# 23D_ESC_DRIVER.net
KiCad netlist of a schematic drawn in Altium Designer
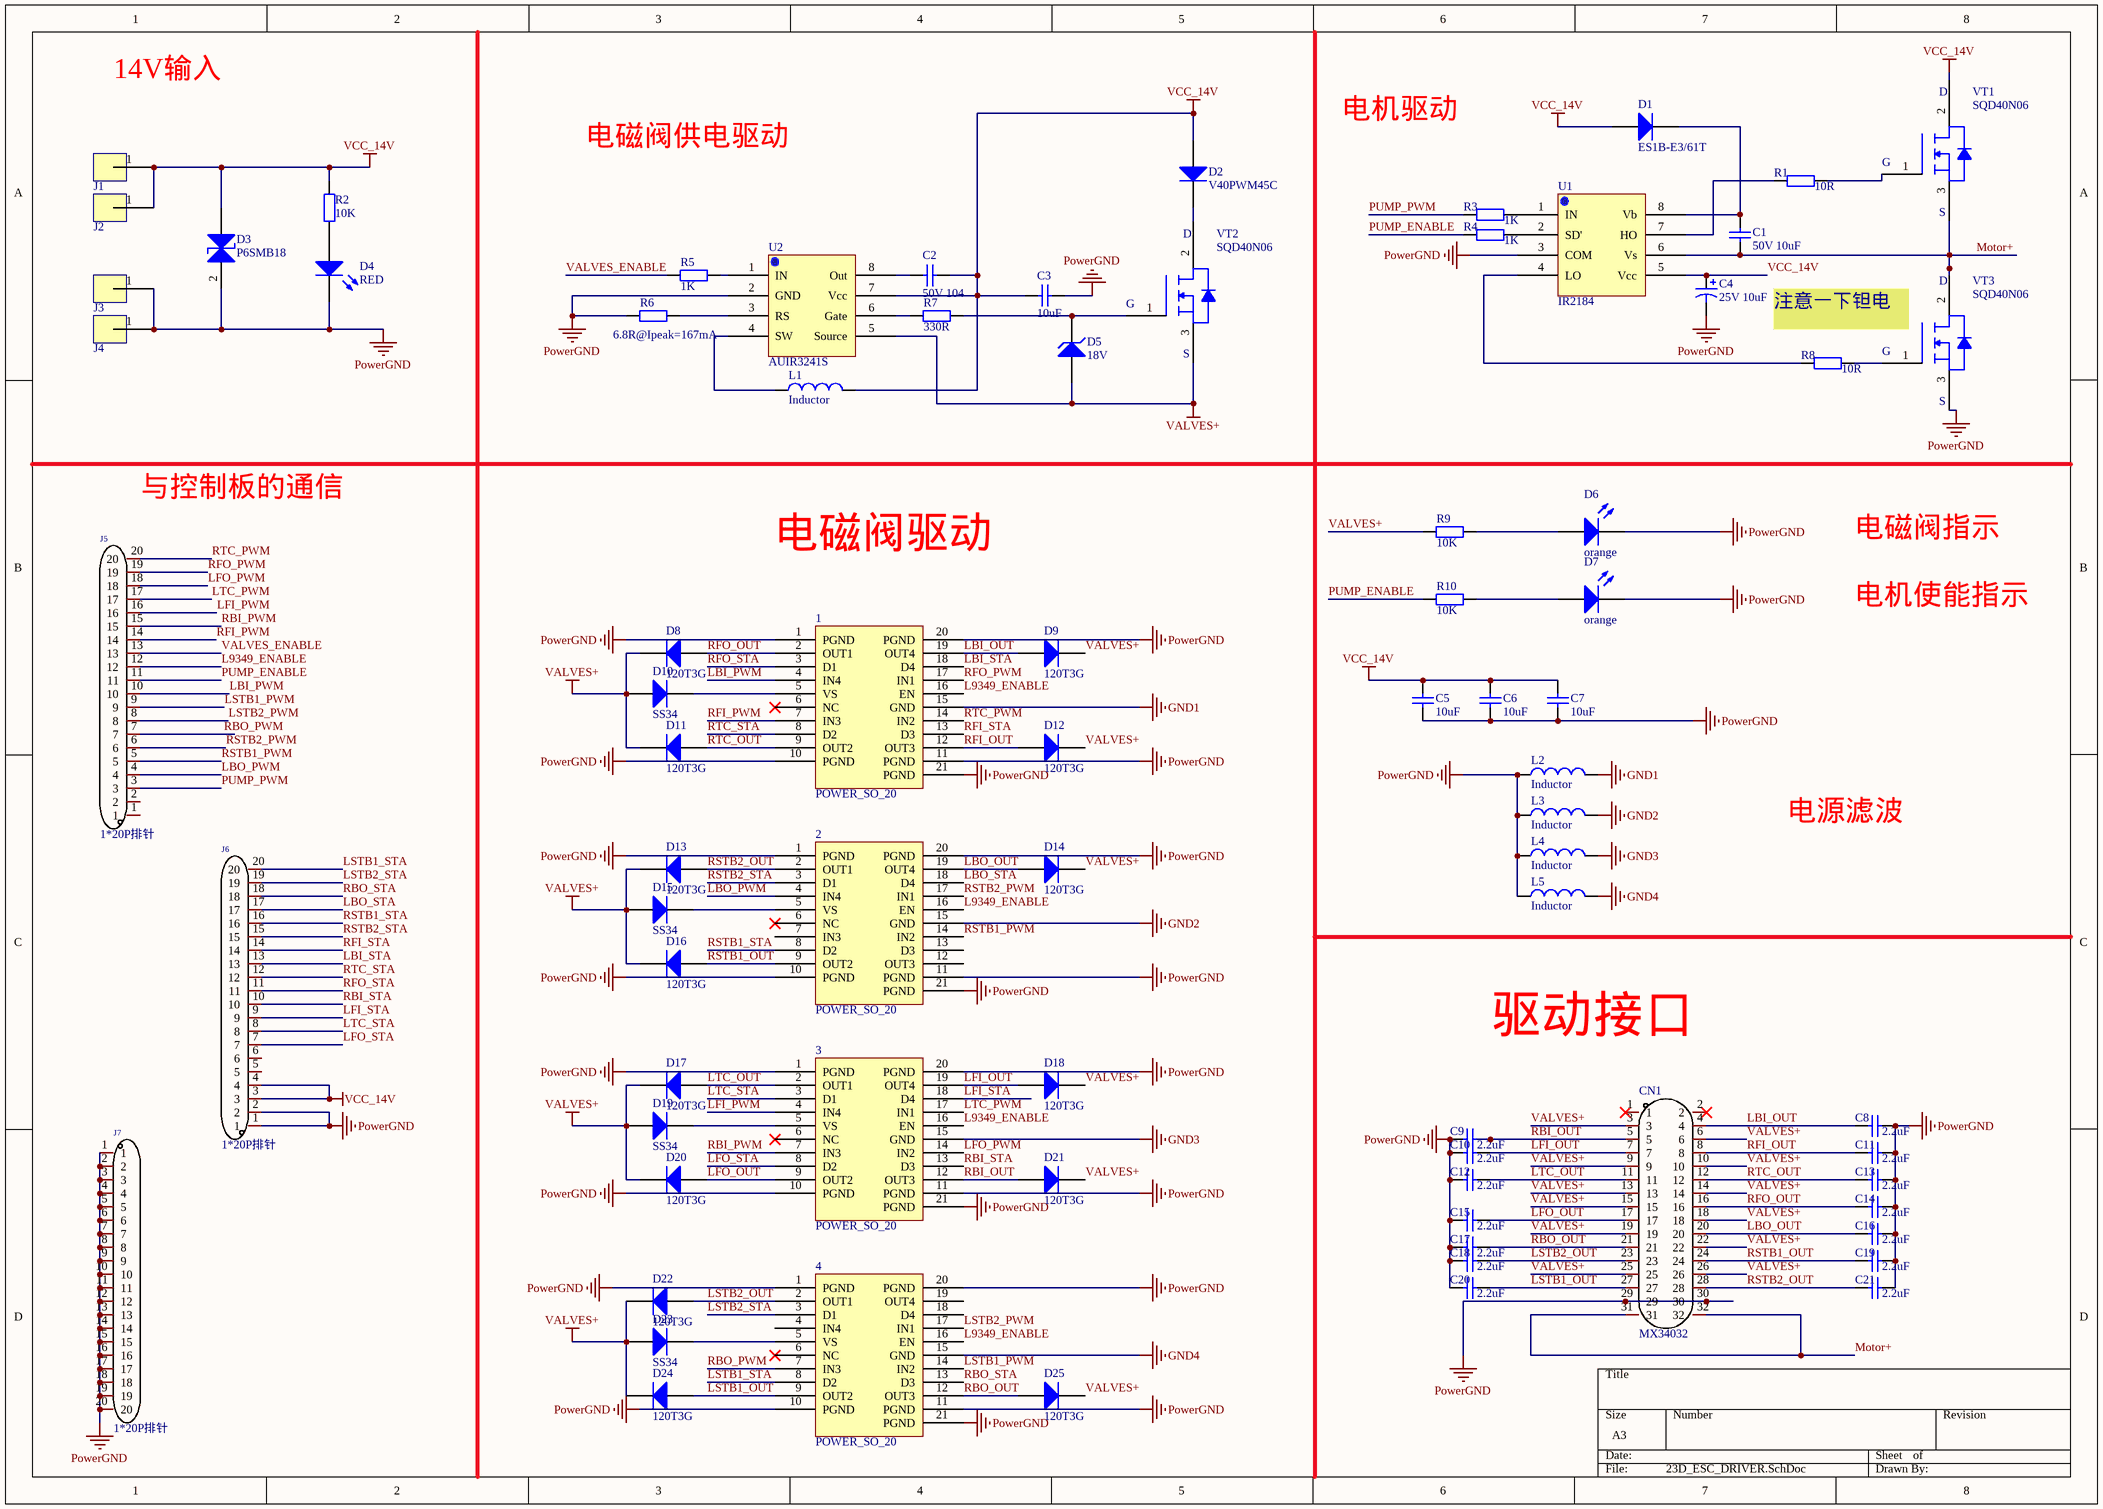
[diagram p0: 23D_ESC_DRIVER.SchDoc]

(export (version "E")
  (design (tool "Eeschema 10.0.6"))
  (components
    (comp (ref "1")
      (value "POWER_SO_20")
      (footprint "POWERSO-20_self_with3D_USEable:POWERSO-20_L15.9-W11.0-P1.27-LS14.2-BL-EP")
      (libsource (lib "PowerSO-20") (part "POWER_SO_20"))
    )
    (comp (ref "2")
      (value "POWER_SO_20")
      (footprint "POWERSO-20_self_with3D_USEable:POWERSO-20_L15.9-W11.0-P1.27-LS14.2-BL-EP")
      (libsource (lib "PowerSO-20") (part "POWER_SO_20"))
    )
    (comp (ref "3")
      (value "POWER_SO_20")
      (footprint "POWERSO-20_self_with3D_USEable:POWERSO-20_L15.9-W11.0-P1.27-LS14.2-BL-EP")
      (libsource (lib "PowerSO-20") (part "POWER_SO_20"))
    )
    (comp (ref "4")
      (value "POWER_SO_20")
      (footprint "POWERSO-20_self_with3D_USEable:POWERSO-20_L15.9-W11.0-P1.27-LS14.2-BL-EP")
      (libsource (lib "PowerSO-20") (part "POWER_SO_20"))
    )
    (comp (ref "C1")
      (value "50V 10uF")
      (footprint "C 0805")
      (description "无极性电容")
      (libsource (lib "HRT_D Schlib") (part "Cap"))
    )
    (comp (ref "C2")
      (value "50V 104")
      (footprint "C 0805")
      (description "无极性电容")
      (libsource (lib "HRT_D Schlib") (part "Cap"))
    )
    (comp (ref "C3")
      (value "10uF")
      (footprint "C 0805")
      (description "无极性电容")
      (libsource (lib "HRT_D Schlib") (part "Cap"))
    )
    (comp (ref "C4")
      (value "25V 10uF")
      (footprint "CP 3528B")
      (description "极性电容")
      (libsource (lib "ER100_ESC") (part "Cap_Pol"))
    )
    (comp (ref "C5")
      (value "10uF")
      (footprint "C 0805")
      (description "无极性电容")
      (libsource (lib "HRT_D Schlib") (part "Cap"))
    )
    (comp (ref "C6")
      (value "10uF")
      (footprint "C 0805")
      (description "无极性电容")
      (libsource (lib "HRT_D Schlib") (part "Cap"))
    )
    (comp (ref "C7")
      (value "10uF")
      (footprint "C 0805")
      (description "无极性电容")
      (libsource (lib "HRT_D Schlib") (part "Cap"))
    )
    (comp (ref "C8")
      (value "2.2uF")
      (footprint "C 0805")
      (description "无极性电容")
      (libsource (lib "HRT_D Schlib") (part "Cap"))
    )
    (comp (ref "C9")
      (value "2.2uF")
      (footprint "C 0805")
      (description "无极性电容")
      (libsource (lib "HRT_D Schlib") (part "Cap"))
    )
    (comp (ref "C10")
      (value "2.2uF")
      (footprint "C 0805")
      (description "无极性电容")
      (libsource (lib "HRT_D Schlib") (part "Cap"))
    )
    (comp (ref "C11")
      (value "2.2uF")
      (footprint "C 0805")
      (description "无极性电容")
      (libsource (lib "HRT_D Schlib") (part "Cap"))
    )
    (comp (ref "C12")
      (value "2.2uF")
      (footprint "C 0805")
      (description "无极性电容")
      (libsource (lib "HRT_D Schlib") (part "Cap"))
    )
    (comp (ref "C13")
      (value "2.2uF")
      (footprint "C 0805")
      (description "无极性电容")
      (libsource (lib "HRT_D Schlib") (part "Cap"))
    )
    (comp (ref "C14")
      (value "2.2uF")
      (footprint "C 0805")
      (description "无极性电容")
      (libsource (lib "HRT_D Schlib") (part "Cap"))
    )
    (comp (ref "C15")
      (value "2.2uF")
      (footprint "C 0805")
      (description "无极性电容")
      (libsource (lib "HRT_D Schlib") (part "Cap"))
    )
    (comp (ref "C16")
      (value "2.2uF")
      (footprint "C 0805")
      (description "无极性电容")
      (libsource (lib "HRT_D Schlib") (part "Cap"))
    )
    (comp (ref "C17")
      (value "2.2uF")
      (footprint "C 0805")
      (description "无极性电容")
      (libsource (lib "HRT_D Schlib") (part "Cap"))
    )
    (comp (ref "C18")
      (value "2.2uF")
      (footprint "C 0805")
      (description "无极性电容")
      (libsource (lib "HRT_D Schlib") (part "Cap"))
    )
    (comp (ref "C19")
      (value "2.2uF")
      (footprint "C 0805")
      (description "无极性电容")
      (libsource (lib "HRT_D Schlib") (part "Cap"))
    )
    (comp (ref "C20")
      (value "2.2uF")
      (footprint "C 0805")
      (description "无极性电容")
      (libsource (lib "HRT_D Schlib") (part "Cap"))
    )
    (comp (ref "C21")
      (value "2.2uF")
      (footprint "C 0805")
      (description "无极性电容")
      (libsource (lib "HRT_D Schlib") (part "Cap"))
    )
    (comp (ref "CN1")
      (value "MX34032NF2")
      (footprint "CONN-TH_MX34032NF2")
      (description "间距:2.2mm;插针结构:2x16P;排数:2;每排PIN数:16;行距:3mm;公母:公型插针;安装方式:弯插;")
      (fields (field (name "MANUFACTURER") "JAE(日本航空电子)") (field (name "NAME") "MX34032"))
      (libsource (lib "MX34032") (part "MX34032NF2"))
    )
    (comp (ref "D1")
      (value "ES1B-E3/61T")
      (footprint "DO-214")
      (description "二极管")
      (libsource (lib "ER100_ESC") (part "Diode"))
    )
    (comp (ref "D2")
      (value "V40PWM45C")
      (footprint "TO252_DIO")
      (description "二极管")
      (libsource (lib "ER100_ESC") (part "Diode"))
    )
    (comp (ref "D3")
      (value "P6SMB18")
      (footprint "DO-214AA")
      (description "BiDir TVS Diode")
      (libsource (lib "ER100_ESC") (part "P6SMBXX"))
    )
    (comp (ref "D4")
      (value "RED")
      (footprint "LED_0805")
      (description "发光二极管")
      (libsource (lib "ESC_control") (part "LED"))
    )
    (comp (ref "D5") (value "18V") (footprint "LL34") (libsource (lib "ER100_ESC") (part "Diode_Zener")))
    (comp (ref "D6")
      (value "orange")
      (footprint "LED_0805")
      (description "发光二极管")
      (libsource (lib "ESC_control") (part "LED"))
    )
    (comp (ref "D7")
      (value "orange")
      (footprint "LED_0805")
      (description "发光二极管")
      (libsource (lib "ESC_control") (part "LED"))
    )
    (comp (ref "D8")
      (value "120T3G")
      (footprint "DO-214")
      (description "二极管")
      (libsource (lib "ER100_ESC") (part "Diode"))
    )
    (comp (ref "D9")
      (value "120T3G")
      (footprint "DO-214")
      (description "二极管")
      (libsource (lib "ER100_ESC") (part "Diode"))
    )
    (comp (ref "D10")
      (value "SS34")
      (footprint "DO-214")
      (description "二极管")
      (libsource (lib "ESC_control") (part "Diode"))
    )
    (comp (ref "D11")
      (value "120T3G")
      (footprint "DO-214")
      (description "二极管")
      (libsource (lib "ER100_ESC") (part "Diode"))
    )
    (comp (ref "D12")
      (value "120T3G")
      (footprint "DO-214")
      (description "二极管")
      (libsource (lib "ER100_ESC") (part "Diode"))
    )
    (comp (ref "D13")
      (value "120T3G")
      (footprint "DO-214")
      (description "二极管")
      (libsource (lib "ER100_ESC") (part "Diode"))
    )
    (comp (ref "D14")
      (value "120T3G")
      (footprint "DO-214")
      (description "二极管")
      (libsource (lib "ER100_ESC") (part "Diode"))
    )
    (comp (ref "D15")
      (value "SS34")
      (footprint "DO-214")
      (description "二极管")
      (libsource (lib "ESC_control") (part "Diode"))
    )
    (comp (ref "D16")
      (value "120T3G")
      (footprint "DO-214")
      (description "二极管")
      (libsource (lib "ER100_ESC") (part "Diode"))
    )
    (comp (ref "D17")
      (value "120T3G")
      (footprint "DO-214")
      (description "二极管")
      (libsource (lib "ER100_ESC") (part "Diode"))
    )
    (comp (ref "D18")
      (value "120T3G")
      (footprint "DO-214")
      (description "二极管")
      (libsource (lib "ER100_ESC") (part "Diode"))
    )
    (comp (ref "D19")
      (value "SS34")
      (footprint "DO-214")
      (description "二极管")
      (libsource (lib "ESC_control") (part "Diode"))
    )
    (comp (ref "D20")
      (value "120T3G")
      (footprint "DO-214")
      (description "二极管")
      (libsource (lib "ER100_ESC") (part "Diode"))
    )
    (comp (ref "D21")
      (value "120T3G")
      (footprint "DO-214")
      (description "二极管")
      (libsource (lib "ER100_ESC") (part "Diode"))
    )
    (comp (ref "D22")
      (value "120T3G")
      (footprint "DO-214")
      (description "二极管")
      (libsource (lib "ER100_ESC") (part "Diode"))
    )
    (comp (ref "D23")
      (value "SS34")
      (footprint "DO-214")
      (description "二极管")
      (libsource (lib "ESC_control") (part "Diode"))
    )
    (comp (ref "D24")
      (value "120T3G")
      (footprint "DO-214")
      (description "二极管")
      (libsource (lib "ER100_ESC") (part "Diode"))
    )
    (comp (ref "D25")
      (value "120T3G")
      (footprint "DO-214")
      (description "二极管")
      (libsource (lib "ER100_ESC") (part "Diode"))
    )
    (comp (ref "J1")
      (value "SMT_Connector")
      (footprint "SMT_Connector")
      (description "表贴接线端")
      (libsource (lib "ER100_ESC") (part "SMT_Connector"))
    )
    (comp (ref "J2")
      (value "SMT_Connector")
      (footprint "SMT_Connector")
      (description "表贴接线端")
      (libsource (lib "ER100_ESC") (part "SMT_Connector"))
    )
    (comp (ref "J3")
      (value "SMT_Connector")
      (footprint "SMT_Connector")
      (description "表贴接线端")
      (libsource (lib "ER100_ESC") (part "SMT_Connector"))
    )
    (comp (ref "J4")
      (value "SMT_Connector")
      (footprint "SMT_Connector")
      (description "表贴接线端")
      (libsource (lib "ER100_ESC") (part "SMT_Connector"))
    )
    (comp (ref "J5")
      (value "2.54-1*20P直针")
      (footprint "HDR-TH_20P-P2.54-V-M-1")
      (fields (field (name "MANUFACTURER") "BOOMELE(博穆精密)") (field (name "NAME") "1*20P排针"))
      (libsource (lib "20P排针2.54mm") (part "2.54-1*20P直针"))
    )
    (comp (ref "J6")
      (value "2.54-1*20P直针")
      (footprint "HDR-TH_20P-P2.54-V-M-1")
      (fields (field (name "MANUFACTURER") "BOOMELE(博穆精密)") (field (name "NAME") "1*20P排针"))
      (libsource (lib "20P排针2.54mm") (part "2.54-1*20P直针"))
    )
    (comp (ref "J7")
      (value "2.54-1*20P直针")
      (footprint "HDR2.54-LI-20P")
      (fields (field (name "MANUFACTURER") "BOOMELE(博穆精密)") (field (name "NAME") "1*20P排针"))
      (libsource (lib "20P排针2.54mm") (part "2.54-1*20P直针"))
    )
    (comp (ref "L1")
      (value "Inductor")
      (footprint "L 0805")
      (description "电感")
      (libsource (lib "HRT_D Schlib") (part "Inductor"))
    )
    (comp (ref "L2")
      (value "Inductor")
      (footprint "L 0805")
      (description "电感")
      (libsource (lib "HRT_D Schlib") (part "Inductor"))
    )
    (comp (ref "L3")
      (value "Inductor")
      (footprint "L 0805")
      (description "电感")
      (libsource (lib "HRT_D Schlib") (part "Inductor"))
    )
    (comp (ref "L4")
      (value "Inductor")
      (footprint "L 0805")
      (description "电感")
      (libsource (lib "HRT_D Schlib") (part "Inductor"))
    )
    (comp (ref "L5")
      (value "Inductor")
      (footprint "L 0805")
      (description "电感")
      (libsource (lib "HRT_D Schlib") (part "Inductor"))
    )
    (comp (ref "R1")
      (value "10R")
      (footprint "R 0805")
      (description "电阻")
      (libsource (lib "HRT_D Schlib") (part "Resistor"))
    )
    (comp (ref "R2")
      (value "10K")
      (footprint "R 0805")
      (description "电阻")
      (libsource (lib "") (part "Resistor_1"))
    )
    (comp (ref "R3")
      (value "1K")
      (footprint "R 0805")
      (description "电阻")
      (libsource (lib "HRT_D Schlib") (part "Resistor"))
    )
    (comp (ref "R4")
      (value "1K")
      (footprint "R 0805")
      (description "电阻")
      (libsource (lib "HRT_D Schlib") (part "Resistor"))
    )
    (comp (ref "R5")
      (value "1K")
      (footprint "R 0805")
      (description "电阻")
      (libsource (lib "HRT_D Schlib") (part "Resistor"))
    )
    (comp (ref "R6")
      (value "6.8R@Ipeak=167mA")
      (footprint "R 0805")
      (description "电阻")
      (libsource (lib "HRT_D Schlib") (part "Resistor"))
    )
    (comp (ref "R7")
      (value "330R")
      (footprint "R 0805")
      (description "电阻")
      (libsource (lib "HRT_D Schlib") (part "Resistor"))
    )
    (comp (ref "R8")
      (value "10R")
      (footprint "R 0805")
      (description "电阻")
      (libsource (lib "HRT_D Schlib") (part "Resistor"))
    )
    (comp (ref "R9")
      (value "10K")
      (footprint "R 0805")
      (description "电阻")
      (libsource (lib "HRT_D Schlib") (part "Resistor"))
    )
    (comp (ref "R10")
      (value "10K")
      (footprint "R 0805")
      (description "电阻")
      (libsource (lib "HRT_D Schlib") (part "Resistor"))
    )
    (comp (ref "U1")
      (value "IR2184")
      (footprint "SOP8")
      (description "Half-Bridge Gate Driver")
      (libsource (lib "ER100_ESC") (part "IR2184"))
    )
    (comp (ref "U2")
      (value "AUIR3241S")
      (footprint "SOP8")
      (description "B2B MOSFET Driver")
      (libsource (lib "ER100_ESC") (part "AUIR3241S"))
    )
    (comp (ref "VT1")
      (value "SQD40N06")
      (footprint "TO263-3B")
      (libsource (lib "ER100_ESC") (part "PowerMos_N"))
    )
    (comp (ref "VT2")
      (value "SQD40N06")
      (footprint "TO252")
      (libsource (lib "ER100_ESC") (part "PowerMos_N"))
    )
    (comp (ref "VT3")
      (value "SQD40N06")
      (footprint "TO263-3B")
      (libsource (lib "ER100_ESC") (part "PowerMos_N"))
    )
  )
  (nets
    (net (code "1") (name "/L9349_ENABLE") (class "Default")
      (node (ref "1") (pin "16") (pinfunction "EN_16") (pintype "passive"))
      (node (ref "2") (pin "16") (pinfunction "EN_16") (pintype "passive"))
      (node (ref "3") (pin "16") (pinfunction "EN_16") (pintype "passive"))
      (node (ref "4") (pin "16") (pinfunction "EN_16") (pintype "passive"))
      (node (ref "J5") (pin "12") (pinfunction "12_12") (pintype "passive"))
    )
    (net (code "2") (name "/LBI_OUT") (class "Default")
      (node (ref "1") (pin "19") (pinfunction "OUT4_19") (pintype "passive"))
      (node (ref "C8") (pin "1") (pinfunction "1_1") (pintype "passive"))
      (node (ref "CN1") (pin "4") (pinfunction "4_4") (pintype "passive"))
      (node (ref "D9") (pin "1") (pinfunction "A_1") (pintype "passive"))
    )
    (net (code "3") (name "/LBI_PWM") (class "Default")
      (node (ref "1") (pin "4") (pinfunction "IN4_4") (pintype "passive"))
      (node (ref "J5") (pin "10") (pinfunction "10_10") (pintype "passive"))
    )
    (net (code "4") (name "/LBI_STA") (class "Default")
      (node (ref "1") (pin "18") (pinfunction "D4_18") (pintype "passive"))
      (node (ref "J6") (pin "13") (pinfunction "13_13") (pintype "passive"))
    )
    (net (code "5") (name "/LBO_OUT") (class "Default")
      (node (ref "2") (pin "19") (pinfunction "OUT4_19") (pintype "passive"))
      (node (ref "C16") (pin "1") (pinfunction "1_1") (pintype "passive"))
      (node (ref "CN1") (pin "20") (pinfunction "20_20") (pintype "passive"))
      (node (ref "D14") (pin "1") (pinfunction "A_1") (pintype "passive"))
    )
    (net (code "6") (name "/LBO_PWM") (class "Default")
      (node (ref "2") (pin "4") (pinfunction "IN4_4") (pintype "passive"))
      (node (ref "J5") (pin "4") (pinfunction "4_4") (pintype "passive"))
    )
    (net (code "7") (name "/LBO_STA") (class "Default")
      (node (ref "2") (pin "18") (pinfunction "D4_18") (pintype "passive"))
      (node (ref "J6") (pin "17") (pinfunction "17_17") (pintype "passive"))
    )
    (net (code "8") (name "/LFI_OUT") (class "Default")
      (node (ref "3") (pin "19") (pinfunction "OUT4_19") (pintype "passive"))
      (node (ref "C10") (pin "2") (pinfunction "2_2") (pintype "passive"))
      (node (ref "CN1") (pin "7") (pinfunction "7_7") (pintype "passive"))
      (node (ref "D18") (pin "1") (pinfunction "A_1") (pintype "passive"))
    )
    (net (code "9") (name "/LFI_PWM") (class "Default")
      (node (ref "3") (pin "4") (pinfunction "IN4_4") (pintype "passive"))
      (node (ref "J5") (pin "16") (pinfunction "16_16") (pintype "passive"))
    )
    (net (code "10") (name "/LFI_STA") (class "Default")
      (node (ref "3") (pin "18") (pinfunction "D4_18") (pintype "passive"))
      (node (ref "J6") (pin "9") (pinfunction "9_9") (pintype "passive"))
    )
    (net (code "11") (name "/LFO_OUT") (class "Default")
      (node (ref "3") (pin "9") (pinfunction "OUT2_9") (pintype "passive"))
      (node (ref "C15") (pin "2") (pinfunction "2_2") (pintype "passive"))
      (node (ref "CN1") (pin "17") (pinfunction "17_17") (pintype "passive"))
      (node (ref "D20") (pin "1") (pinfunction "A_1") (pintype "passive"))
    )
    (net (code "12") (name "/LFO_PWM") (class "Default")
      (node (ref "3") (pin "14") (pinfunction "IN2_14") (pintype "passive"))
      (node (ref "J5") (pin "18") (pinfunction "18_18") (pintype "passive"))
    )
    (net (code "13") (name "/LFO_STA") (class "Default")
      (node (ref "3") (pin "8") (pinfunction "D2_8") (pintype "passive"))
      (node (ref "J6") (pin "7") (pinfunction "7_7") (pintype "passive"))
    )
    (net (code "14") (name "/LSTB1_OUT") (class "Default")
      (node (ref "4") (pin "9") (pinfunction "OUT2_9") (pintype "passive"))
      (node (ref "C20") (pin "2") (pinfunction "2_2") (pintype "passive"))
      (node (ref "CN1") (pin "27") (pinfunction "27_27") (pintype "passive"))
      (node (ref "D24") (pin "1") (pinfunction "A_1") (pintype "passive"))
    )
    (net (code "15") (name "/LSTB1_PWM") (class "Default")
      (node (ref "4") (pin "14") (pinfunction "IN2_14") (pintype "passive"))
      (node (ref "J5") (pin "9") (pinfunction "9_9") (pintype "passive"))
    )
    (net (code "16") (name "/LSTB1_STA") (class "Default")
      (node (ref "4") (pin "8") (pinfunction "D2_8") (pintype "passive"))
      (node (ref "J6") (pin "20") (pinfunction "20_20") (pintype "passive"))
    )
    (net (code "17") (name "/LSTB2_OUT") (class "Default")
      (node (ref "4") (pin "2") (pinfunction "OUT1_2") (pintype "passive"))
      (node (ref "C18") (pin "2") (pinfunction "2_2") (pintype "passive"))
      (node (ref "CN1") (pin "23") (pinfunction "23_23") (pintype "passive"))
      (node (ref "D22") (pin "1") (pinfunction "A_1") (pintype "passive"))
    )
    (net (code "18") (name "/LSTB2_PWM") (class "Default")
      (node (ref "4") (pin "17") (pinfunction "IN1_17") (pintype "passive"))
      (node (ref "J5") (pin "8") (pinfunction "8_8") (pintype "passive"))
    )
    (net (code "19") (name "/LSTB2_STA") (class "Default")
      (node (ref "4") (pin "3") (pinfunction "D1_3") (pintype "passive"))
      (node (ref "J6") (pin "19") (pinfunction "19_19") (pintype "passive"))
    )
    (net (code "20") (name "/LTC_OUT") (class "Default")
      (node (ref "3") (pin "2") (pinfunction "OUT1_2") (pintype "passive"))
      (node (ref "C12") (pin "2") (pinfunction "2_2") (pintype "passive"))
      (node (ref "CN1") (pin "11") (pinfunction "11_11") (pintype "passive"))
      (node (ref "D17") (pin "1") (pinfunction "A_1") (pintype "passive"))
    )
    (net (code "21") (name "/LTC_PWM") (class "Default")
      (node (ref "3") (pin "17") (pinfunction "IN1_17") (pintype "passive"))
      (node (ref "J5") (pin "17") (pinfunction "17_17") (pintype "passive"))
    )
    (net (code "22") (name "/LTC_STA") (class "Default")
      (node (ref "3") (pin "3") (pinfunction "D1_3") (pintype "passive"))
      (node (ref "J6") (pin "8") (pinfunction "8_8") (pintype "passive"))
    )
    (net (code "23") (name "/Motor+") (class "Default")
      (node (ref "C1") (pin "1") (pinfunction "1_1") (pintype "passive"))
      (node (ref "CN1") (pin "31") (pinfunction "31_31") (pintype "passive"))
      (node (ref "CN1") (pin "32") (pinfunction "32_32") (pintype "passive"))
      (node (ref "U1") (pin "6") (pinfunction "Vs_6") (pintype "passive"))
      (node (ref "VT1") (pin "3") (pinfunction "3_3") (pintype "passive"))
      (node (ref "VT3") (pin "2") (pinfunction "2_2") (pintype "passive"))
    )
    (net (code "24") (name "/PUMP_ENABLE") (class "Default")
      (node (ref "J5") (pin "11") (pinfunction "11_11") (pintype "passive"))
      (node (ref "R10") (pin "1") (pinfunction "1_1") (pintype "passive"))
      (node (ref "R4") (pin "1") (pinfunction "1_1") (pintype "passive"))
    )
    (net (code "25") (name "/PUMP_PWM") (class "Default")
      (node (ref "J5") (pin "3") (pinfunction "3_3") (pintype "passive"))
      (node (ref "R3") (pin "1") (pinfunction "1_1") (pintype "passive"))
    )
    (net (code "26") (name "/RBI_OUT") (class "Default")
      (node (ref "3") (pin "12") (pinfunction "OUT3_12") (pintype "passive"))
      (node (ref "C9") (pin "2") (pinfunction "2_2") (pintype "passive"))
      (node (ref "CN1") (pin "5") (pinfunction "5_5") (pintype "passive"))
      (node (ref "D21") (pin "1") (pinfunction "A_1") (pintype "passive"))
    )
    (net (code "27") (name "/RBI_PWM") (class "Default")
      (node (ref "3") (pin "7") (pinfunction "IN3_7") (pintype "passive"))
      (node (ref "J5") (pin "15") (pinfunction "15_15") (pintype "passive"))
    )
    (net (code "28") (name "/RBI_STA") (class "Default")
      (node (ref "3") (pin "13") (pinfunction "D3_13") (pintype "passive"))
      (node (ref "J6") (pin "10") (pinfunction "10_10") (pintype "passive"))
    )
    (net (code "29") (name "/RBO_OUT") (class "Default")
      (node (ref "4") (pin "12") (pinfunction "OUT3_12") (pintype "passive"))
      (node (ref "C17") (pin "2") (pinfunction "2_2") (pintype "passive"))
      (node (ref "CN1") (pin "21") (pinfunction "21_21") (pintype "passive"))
      (node (ref "D25") (pin "1") (pinfunction "A_1") (pintype "passive"))
    )
    (net (code "30") (name "/RBO_PWM") (class "Default")
      (node (ref "4") (pin "7") (pinfunction "IN3_7") (pintype "passive"))
      (node (ref "J5") (pin "7") (pinfunction "7_7") (pintype "passive"))
    )
    (net (code "31") (name "/RBO_STA") (class "Default")
      (node (ref "4") (pin "13") (pinfunction "D3_13") (pintype "passive"))
      (node (ref "J6") (pin "18") (pinfunction "18_18") (pintype "passive"))
    )
    (net (code "32") (name "/RFI_OUT") (class "Default")
      (node (ref "1") (pin "12") (pinfunction "OUT3_12") (pintype "passive"))
      (node (ref "C11") (pin "1") (pinfunction "1_1") (pintype "passive"))
      (node (ref "CN1") (pin "8") (pinfunction "8_8") (pintype "passive"))
      (node (ref "D12") (pin "1") (pinfunction "A_1") (pintype "passive"))
    )
    (net (code "33") (name "/RFI_PWM") (class "Default")
      (node (ref "1") (pin "7") (pinfunction "IN3_7") (pintype "passive"))
      (node (ref "J5") (pin "14") (pinfunction "14_14") (pintype "passive"))
    )
    (net (code "34") (name "/RFI_STA") (class "Default")
      (node (ref "1") (pin "13") (pinfunction "D3_13") (pintype "passive"))
      (node (ref "J6") (pin "14") (pinfunction "14_14") (pintype "passive"))
    )
    (net (code "35") (name "/RFO_OUT") (class "Default")
      (node (ref "1") (pin "2") (pinfunction "OUT1_2") (pintype "passive"))
      (node (ref "C14") (pin "1") (pinfunction "1_1") (pintype "passive"))
      (node (ref "CN1") (pin "16") (pinfunction "16_16") (pintype "passive"))
      (node (ref "D8") (pin "1") (pinfunction "A_1") (pintype "passive"))
    )
    (net (code "36") (name "/RFO_PWM") (class "Default")
      (node (ref "1") (pin "17") (pinfunction "IN1_17") (pintype "passive"))
      (node (ref "J5") (pin "19") (pinfunction "19_19") (pintype "passive"))
    )
    (net (code "37") (name "/RFO_STA") (class "Default")
      (node (ref "1") (pin "3") (pinfunction "D1_3") (pintype "passive"))
      (node (ref "J6") (pin "11") (pinfunction "11_11") (pintype "passive"))
    )
    (net (code "38") (name "/RSTB1_OUT") (class "Default")
      (node (ref "2") (pin "9") (pinfunction "OUT2_9") (pintype "passive"))
      (node (ref "C19") (pin "1") (pinfunction "1_1") (pintype "passive"))
      (node (ref "CN1") (pin "24") (pinfunction "24_24") (pintype "passive"))
      (node (ref "D16") (pin "1") (pinfunction "A_1") (pintype "passive"))
    )
    (net (code "39") (name "/RSTB1_PWM") (class "Default")
      (node (ref "2") (pin "14") (pinfunction "IN2_14") (pintype "passive"))
      (node (ref "J5") (pin "5") (pinfunction "5_5") (pintype "passive"))
    )
    (net (code "40") (name "/RSTB1_STA") (class "Default")
      (node (ref "2") (pin "8") (pinfunction "D2_8") (pintype "passive"))
      (node (ref "J6") (pin "16") (pinfunction "16_16") (pintype "passive"))
    )
    (net (code "41") (name "/RSTB2_OUT") (class "Default")
      (node (ref "2") (pin "2") (pinfunction "OUT1_2") (pintype "passive"))
      (node (ref "C21") (pin "1") (pinfunction "1_1") (pintype "passive"))
      (node (ref "CN1") (pin "28") (pinfunction "28_28") (pintype "passive"))
      (node (ref "D13") (pin "1") (pinfunction "A_1") (pintype "passive"))
    )
    (net (code "42") (name "/RSTB2_PWM") (class "Default")
      (node (ref "2") (pin "17") (pinfunction "IN1_17") (pintype "passive"))
      (node (ref "J5") (pin "6") (pinfunction "6_6") (pintype "passive"))
    )
    (net (code "43") (name "/RSTB2_STA") (class "Default")
      (node (ref "2") (pin "3") (pinfunction "D1_3") (pintype "passive"))
      (node (ref "J6") (pin "15") (pinfunction "15_15") (pintype "passive"))
    )
    (net (code "44") (name "/RTC_OUT") (class "Default")
      (node (ref "1") (pin "9") (pinfunction "OUT2_9") (pintype "passive"))
      (node (ref "C13") (pin "1") (pinfunction "1_1") (pintype "passive"))
      (node (ref "CN1") (pin "12") (pinfunction "12_12") (pintype "passive"))
      (node (ref "D11") (pin "1") (pinfunction "A_1") (pintype "passive"))
    )
    (net (code "45") (name "/RTC_PWM") (class "Default")
      (node (ref "1") (pin "14") (pinfunction "IN2_14") (pintype "passive"))
      (node (ref "J5") (pin "20") (pinfunction "20_20") (pintype "passive"))
    )
    (net (code "46") (name "/RTC_STA") (class "Default")
      (node (ref "1") (pin "8") (pinfunction "D2_8") (pintype "passive"))
      (node (ref "J6") (pin "12") (pinfunction "12_12") (pintype "passive"))
    )
    (net (code "47") (name "/VALVES_ENABLE") (class "Default")
      (node (ref "J5") (pin "13") (pinfunction "13_13") (pintype "passive"))
      (node (ref "R5") (pin "1") (pinfunction "1_1") (pintype "passive"))
    )
    (net (code "48") (name "GND1") (class "Default")
      (node (ref "1") (pin "15") (pinfunction "GND_15") (pintype "passive"))
      (node (ref "L2") (pin "2") (pinfunction "2_2") (pintype "passive"))
    )
    (net (code "49") (name "GND2") (class "Default")
      (node (ref "2") (pin "15") (pinfunction "GND_15") (pintype "passive"))
      (node (ref "L3") (pin "2") (pinfunction "2_2") (pintype "passive"))
    )
    (net (code "50") (name "GND3") (class "Default")
      (node (ref "3") (pin "15") (pinfunction "GND_15") (pintype "passive"))
      (node (ref "L4") (pin "2") (pinfunction "2_2") (pintype "passive"))
    )
    (net (code "51") (name "GND4") (class "Default")
      (node (ref "4") (pin "15") (pinfunction "GND_15") (pintype "passive"))
      (node (ref "L5") (pin "2") (pinfunction "2_2") (pintype "passive"))
    )
    (net (code "52") (name "Net-(1-VS)") (class "Default")
      (node (ref "1") (pin "5") (pinfunction "VS_5") (pintype "passive"))
      (node (ref "D10") (pin "2") (pinfunction "K_2") (pintype "passive"))
    )
    (net (code "53") (name "Net-(2-VS)") (class "Default")
      (node (ref "2") (pin "5") (pinfunction "VS_5") (pintype "passive"))
      (node (ref "D15") (pin "2") (pinfunction "K_2") (pintype "passive"))
    )
    (net (code "54") (name "Net-(3-VS)") (class "Default")
      (node (ref "3") (pin "5") (pinfunction "VS_5") (pintype "passive"))
      (node (ref "D19") (pin "2") (pinfunction "K_2") (pintype "passive"))
    )
    (net (code "55") (name "Net-(4-VS)") (class "Default")
      (node (ref "4") (pin "5") (pinfunction "VS_5") (pintype "passive"))
      (node (ref "D23") (pin "2") (pinfunction "K_2") (pintype "passive"))
    )
    (net (code "56") (name "Net-(D1-K)") (class "Default")
      (node (ref "C1") (pin "2") (pinfunction "2_2") (pintype "passive"))
      (node (ref "D1") (pin "2") (pinfunction "K_2") (pintype "passive"))
      (node (ref "U1") (pin "8") (pinfunction "Vb_8") (pintype "passive"))
    )
    (net (code "57") (name "Net-(D2-K)") (class "Default")
      (node (ref "D2") (pin "2") (pinfunction "K_2") (pintype "passive"))
      (node (ref "VT2") (pin "2") (pinfunction "2_2") (pintype "passive"))
    )
    (net (code "58") (name "Net-(D4-A)") (class "Default")
      (node (ref "D4") (pin "1") (pinfunction "A_1") (pintype "passive"))
      (node (ref "R2") (pin "1") (pinfunction "1_1") (pintype "passive"))
    )
    (net (code "59") (name "Net-(D5-K)") (class "Default")
      (node (ref "D5") (pin "2") (pinfunction "K_2") (pintype "passive"))
      (node (ref "R7") (pin "2") (pinfunction "2_2") (pintype "passive"))
      (node (ref "VT2") (pin "1") (pinfunction "G_1") (pintype "passive"))
    )
    (net (code "60") (name "Net-(D6-A)") (class "Default")
      (node (ref "D6") (pin "1") (pinfunction "A_1") (pintype "passive"))
      (node (ref "R9") (pin "2") (pinfunction "2_2") (pintype "passive"))
    )
    (net (code "61") (name "Net-(D7-A)") (class "Default")
      (node (ref "D7") (pin "1") (pinfunction "A_1") (pintype "passive"))
      (node (ref "R10") (pin "2") (pinfunction "2_2") (pintype "passive"))
    )
    (net (code "62") (name "Net-(U1-HO)") (class "Default")
      (node (ref "R1") (pin "1") (pinfunction "1_1") (pintype "passive"))
      (node (ref "U1") (pin "7") (pinfunction "HO_7") (pintype "passive"))
    )
    (net (code "63") (name "Net-(U1-IN)") (class "Default")
      (node (ref "R3") (pin "2") (pinfunction "2_2") (pintype "passive"))
      (node (ref "U1") (pin "1") (pinfunction "IN_1") (pintype "passive"))
    )
    (net (code "64") (name "Net-(U1-LO)") (class "Default")
      (node (ref "R8") (pin "1") (pinfunction "1_1") (pintype "passive"))
      (node (ref "U1") (pin "4") (pinfunction "LO_4") (pintype "passive"))
    )
    (net (code "65") (name "Net-(U1-SD')") (class "Default")
      (node (ref "R4") (pin "2") (pinfunction "2_2") (pintype "passive"))
      (node (ref "U1") (pin "2") (pinfunction "SD'_2") (pintype "passive"))
    )
    (net (code "66") (name "Net-(U2-Gate)") (class "Default")
      (node (ref "R7") (pin "1") (pinfunction "1_1") (pintype "passive"))
      (node (ref "U2") (pin "6") (pinfunction "Gate_6") (pintype "passive"))
    )
    (net (code "67") (name "Net-(U2-IN)") (class "Default")
      (node (ref "R5") (pin "2") (pinfunction "2_2") (pintype "passive"))
      (node (ref "U2") (pin "1") (pinfunction "IN_1") (pintype "passive"))
    )
    (net (code "68") (name "Net-(U2-Out)") (class "Default")
      (node (ref "C2") (pin "1") (pinfunction "1_1") (pintype "passive"))
      (node (ref "U2") (pin "8") (pinfunction "Out_8") (pintype "passive"))
    )
    (net (code "69") (name "Net-(U2-RS)") (class "Default")
      (node (ref "R6") (pin "2") (pinfunction "2_2") (pintype "passive"))
      (node (ref "U2") (pin "3") (pinfunction "RS_3") (pintype "passive"))
    )
    (net (code "70") (name "Net-(U2-SW)") (class "Default")
      (node (ref "L1") (pin "1") (pinfunction "1_1") (pintype "passive"))
      (node (ref "U2") (pin "4") (pinfunction "SW_4") (pintype "passive"))
    )
    (net (code "71") (name "Net-(VT1-G)") (class "Default")
      (node (ref "R1") (pin "2") (pinfunction "2_2") (pintype "passive"))
      (node (ref "VT1") (pin "1") (pinfunction "G_1") (pintype "passive"))
    )
    (net (code "72") (name "Net-(VT3-G)") (class "Default")
      (node (ref "R8") (pin "2") (pinfunction "2_2") (pintype "passive"))
      (node (ref "VT3") (pin "1") (pinfunction "G_1") (pintype "passive"))
    )
    (net (code "73") (name "PowerGND") (class "Default")
      (node (ref "1") (pin "1") (pinfunction "PGND_1") (pintype "passive"))
      (node (ref "1") (pin "10") (pinfunction "PGND_10") (pintype "passive"))
      (node (ref "1") (pin "11") (pinfunction "PGND_11") (pintype "passive"))
      (node (ref "1") (pin "20") (pinfunction "PGND_20") (pintype "passive"))
      (node (ref "1") (pin "21") (pinfunction "PGND_21") (pintype "passive"))
      (node (ref "2") (pin "1") (pinfunction "PGND_1") (pintype "passive"))
      (node (ref "2") (pin "10") (pinfunction "PGND_10") (pintype "passive"))
      (node (ref "2") (pin "11") (pinfunction "PGND_11") (pintype "passive"))
      (node (ref "2") (pin "20") (pinfunction "PGND_20") (pintype "passive"))
      (node (ref "2") (pin "21") (pinfunction "PGND_21") (pintype "passive"))
      (node (ref "3") (pin "1") (pinfunction "PGND_1") (pintype "passive"))
      (node (ref "3") (pin "10") (pinfunction "PGND_10") (pintype "passive"))
      (node (ref "3") (pin "11") (pinfunction "PGND_11") (pintype "passive"))
      (node (ref "3") (pin "20") (pinfunction "PGND_20") (pintype "passive"))
      (node (ref "3") (pin "21") (pinfunction "PGND_21") (pintype "passive"))
      (node (ref "4") (pin "1") (pinfunction "PGND_1") (pintype "passive"))
      (node (ref "4") (pin "10") (pinfunction "PGND_10") (pintype "passive"))
      (node (ref "4") (pin "11") (pinfunction "PGND_11") (pintype "passive"))
      (node (ref "4") (pin "20") (pinfunction "PGND_20") (pintype "passive"))
      (node (ref "4") (pin "21") (pinfunction "PGND_21") (pintype "passive"))
      (node (ref "C10") (pin "1") (pinfunction "1_1") (pintype "passive"))
      (node (ref "C11") (pin "2") (pinfunction "2_2") (pintype "passive"))
      (node (ref "C12") (pin "1") (pinfunction "1_1") (pintype "passive"))
      (node (ref "C13") (pin "2") (pinfunction "2_2") (pintype "passive"))
      (node (ref "C14") (pin "2") (pinfunction "2_2") (pintype "passive"))
      (node (ref "C15") (pin "1") (pinfunction "1_1") (pintype "passive"))
      (node (ref "C16") (pin "2") (pinfunction "2_2") (pintype "passive"))
      (node (ref "C17") (pin "1") (pinfunction "1_1") (pintype "passive"))
      (node (ref "C18") (pin "1") (pinfunction "1_1") (pintype "passive"))
      (node (ref "C19") (pin "2") (pinfunction "2_2") (pintype "passive"))
      (node (ref "C20") (pin "1") (pinfunction "1_1") (pintype "passive"))
      (node (ref "C21") (pin "2") (pinfunction "2_2") (pintype "passive"))
      (node (ref "C3") (pin "2") (pinfunction "2_2") (pintype "passive"))
      (node (ref "C4") (pin "2") (pinfunction "2_2") (pintype "passive"))
      (node (ref "C5") (pin "1") (pinfunction "1_1") (pintype "passive"))
      (node (ref "C6") (pin "1") (pinfunction "1_1") (pintype "passive"))
      (node (ref "C7") (pin "1") (pinfunction "1_1") (pintype "passive"))
      (node (ref "C8") (pin "2") (pinfunction "2_2") (pintype "passive"))
      (node (ref "C9") (pin "1") (pinfunction "1_1") (pintype "passive"))
      (node (ref "CN1") (pin "29") (pinfunction "29_29") (pintype "passive"))
      (node (ref "CN1") (pin "30") (pinfunction "30_30") (pintype "passive"))
      (node (ref "D3") (pin "2") (pinfunction "K_2") (pintype "passive"))
      (node (ref "D4") (pin "2") (pinfunction "K_2") (pintype "passive"))
      (node (ref "D6") (pin "2") (pinfunction "K_2") (pintype "passive"))
      (node (ref "D7") (pin "2") (pinfunction "K_2") (pintype "passive"))
      (node (ref "J3") (pin "1") (pinfunction "1_1") (pintype "passive"))
      (node (ref "J4") (pin "1") (pinfunction "1_1") (pintype "passive"))
      (node (ref "J6") (pin "1") (pinfunction "1_1") (pintype "passive"))
      (node (ref "J6") (pin "2") (pinfunction "2_2") (pintype "passive"))
      (node (ref "J7") (pin "1") (pinfunction "1_1") (pintype "passive"))
      (node (ref "J7") (pin "10") (pinfunction "10_10") (pintype "passive"))
      (node (ref "J7") (pin "11") (pinfunction "11_11") (pintype "passive"))
      (node (ref "J7") (pin "12") (pinfunction "12_12") (pintype "passive"))
      (node (ref "J7") (pin "13") (pinfunction "13_13") (pintype "passive"))
      (node (ref "J7") (pin "14") (pinfunction "14_14") (pintype "passive"))
      (node (ref "J7") (pin "15") (pinfunction "15_15") (pintype "passive"))
      (node (ref "J7") (pin "16") (pinfunction "16_16") (pintype "passive"))
      (node (ref "J7") (pin "17") (pinfunction "17_17") (pintype "passive"))
      (node (ref "J7") (pin "18") (pinfunction "18_18") (pintype "passive"))
      (node (ref "J7") (pin "19") (pinfunction "19_19") (pintype "passive"))
      (node (ref "J7") (pin "2") (pinfunction "2_2") (pintype "passive"))
      (node (ref "J7") (pin "20") (pinfunction "20_20") (pintype "passive"))
      (node (ref "J7") (pin "3") (pinfunction "3_3") (pintype "passive"))
      (node (ref "J7") (pin "4") (pinfunction "4_4") (pintype "passive"))
      (node (ref "J7") (pin "5") (pinfunction "5_5") (pintype "passive"))
      (node (ref "J7") (pin "6") (pinfunction "6_6") (pintype "passive"))
      (node (ref "J7") (pin "7") (pinfunction "7_7") (pintype "passive"))
      (node (ref "J7") (pin "8") (pinfunction "8_8") (pintype "passive"))
      (node (ref "J7") (pin "9") (pinfunction "9_9") (pintype "passive"))
      (node (ref "L2") (pin "1") (pinfunction "1_1") (pintype "passive"))
      (node (ref "L3") (pin "1") (pinfunction "1_1") (pintype "passive"))
      (node (ref "L4") (pin "1") (pinfunction "1_1") (pintype "passive"))
      (node (ref "L5") (pin "1") (pinfunction "1_1") (pintype "passive"))
      (node (ref "R6") (pin "1") (pinfunction "1_1") (pintype "passive"))
      (node (ref "U1") (pin "3") (pinfunction "COM_3") (pintype "passive"))
      (node (ref "U2") (pin "2") (pinfunction "GND_2") (pintype "passive"))
      (node (ref "VT3") (pin "3") (pinfunction "3_3") (pintype "passive"))
    )
    (net (code "74") (name "VALVES+") (class "Default")
      (node (ref "CN1") (pin "10") (pinfunction "10_10") (pintype "passive"))
      (node (ref "CN1") (pin "13") (pinfunction "13_13") (pintype "passive"))
      (node (ref "CN1") (pin "14") (pinfunction "14_14") (pintype "passive"))
      (node (ref "CN1") (pin "15") (pinfunction "15_15") (pintype "passive"))
      (node (ref "CN1") (pin "18") (pinfunction "18_18") (pintype "passive"))
      (node (ref "CN1") (pin "19") (pinfunction "19_19") (pintype "passive"))
      (node (ref "CN1") (pin "22") (pinfunction "22_22") (pintype "passive"))
      (node (ref "CN1") (pin "25") (pinfunction "25_25") (pintype "passive"))
      (node (ref "CN1") (pin "26") (pinfunction "26_26") (pintype "passive"))
      (node (ref "CN1") (pin "3") (pinfunction "3_3") (pintype "passive"))
      (node (ref "CN1") (pin "6") (pinfunction "6_6") (pintype "passive"))
      (node (ref "CN1") (pin "9") (pinfunction "9_9") (pintype "passive"))
      (node (ref "D10") (pin "1") (pinfunction "A_1") (pintype "passive"))
      (node (ref "D11") (pin "2") (pinfunction "K_2") (pintype "passive"))
      (node (ref "D12") (pin "2") (pinfunction "K_2") (pintype "passive"))
      (node (ref "D13") (pin "2") (pinfunction "K_2") (pintype "passive"))
      (node (ref "D14") (pin "2") (pinfunction "K_2") (pintype "passive"))
      (node (ref "D15") (pin "1") (pinfunction "A_1") (pintype "passive"))
      (node (ref "D16") (pin "2") (pinfunction "K_2") (pintype "passive"))
      (node (ref "D17") (pin "2") (pinfunction "K_2") (pintype "passive"))
      (node (ref "D18") (pin "2") (pinfunction "K_2") (pintype "passive"))
      (node (ref "D19") (pin "1") (pinfunction "A_1") (pintype "passive"))
      (node (ref "D20") (pin "2") (pinfunction "K_2") (pintype "passive"))
      (node (ref "D21") (pin "2") (pinfunction "K_2") (pintype "passive"))
      (node (ref "D22") (pin "2") (pinfunction "K_2") (pintype "passive"))
      (node (ref "D23") (pin "1") (pinfunction "A_1") (pintype "passive"))
      (node (ref "D24") (pin "2") (pinfunction "K_2") (pintype "passive"))
      (node (ref "D25") (pin "2") (pinfunction "K_2") (pintype "passive"))
      (node (ref "D5") (pin "1") (pinfunction "A_1") (pintype "passive"))
      (node (ref "D8") (pin "2") (pinfunction "K_2") (pintype "passive"))
      (node (ref "D9") (pin "2") (pinfunction "K_2") (pintype "passive"))
      (node (ref "R9") (pin "1") (pinfunction "1_1") (pintype "passive"))
      (node (ref "U2") (pin "5") (pinfunction "Source_5") (pintype "passive"))
      (node (ref "VT2") (pin "3") (pinfunction "3_3") (pintype "passive"))
    )
    (net (code "75") (name "VCC_14V") (class "Default")
      (node (ref "C2") (pin "2") (pinfunction "2_2") (pintype "passive"))
      (node (ref "C3") (pin "1") (pinfunction "1_1") (pintype "passive"))
      (node (ref "C4") (pin "1") (pinfunction "1_1") (pintype "passive"))
      (node (ref "C5") (pin "2") (pinfunction "2_2") (pintype "passive"))
      (node (ref "C6") (pin "2") (pinfunction "2_2") (pintype "passive"))
      (node (ref "C7") (pin "2") (pinfunction "2_2") (pintype "passive"))
      (node (ref "D1") (pin "1") (pinfunction "A_1") (pintype "passive"))
      (node (ref "D2") (pin "1") (pinfunction "A_1") (pintype "passive"))
      (node (ref "D3") (pin "1") (pinfunction "A_1") (pintype "passive"))
      (node (ref "J1") (pin "1") (pinfunction "1_1") (pintype "passive"))
      (node (ref "J2") (pin "1") (pinfunction "1_1") (pintype "passive"))
      (node (ref "J6") (pin "3") (pinfunction "3_3") (pintype "passive"))
      (node (ref "J6") (pin "4") (pinfunction "4_4") (pintype "passive"))
      (node (ref "L1") (pin "2") (pinfunction "2_2") (pintype "passive"))
      (node (ref "R2") (pin "2") (pinfunction "2_2") (pintype "passive"))
      (node (ref "U1") (pin "5") (pinfunction "Vcc_5") (pintype "passive"))
      (node (ref "U2") (pin "7") (pinfunction "Vcc_7") (pintype "passive"))
      (node (ref "VT1") (pin "2") (pinfunction "2_2") (pintype "passive"))
    )
    (net (code "76") (name "unconnected-(1-NC-Pad6)") (class "Default")
      (node (ref "1") (pin "6") (pinfunction "NC_6") (pintype "passive+no_connect"))
    )
    (net (code "77") (name "unconnected-(2-D3-Pad13)") (class "Default")
      (node (ref "2") (pin "13") (pinfunction "D3_13") (pintype "passive"))
    )
    (net (code "78") (name "unconnected-(2-IN3-Pad7)") (class "Default")
      (node (ref "2") (pin "7") (pinfunction "IN3_7") (pintype "passive"))
    )
    (net (code "79") (name "unconnected-(2-NC-Pad6)") (class "Default")
      (node (ref "2") (pin "6") (pinfunction "NC_6") (pintype "passive+no_connect"))
    )
    (net (code "80") (name "unconnected-(2-OUT3-Pad12)") (class "Default")
      (node (ref "2") (pin "12") (pinfunction "OUT3_12") (pintype "passive"))
    )
    (net (code "81") (name "unconnected-(3-NC-Pad6)") (class "Default")
      (node (ref "3") (pin "6") (pinfunction "NC_6") (pintype "passive+no_connect"))
    )
    (net (code "82") (name "unconnected-(4-D4-Pad18)") (class "Default")
      (node (ref "4") (pin "18") (pinfunction "D4_18") (pintype "passive"))
    )
    (net (code "83") (name "unconnected-(4-IN4-Pad4)") (class "Default")
      (node (ref "4") (pin "4") (pinfunction "IN4_4") (pintype "passive"))
    )
    (net (code "84") (name "unconnected-(4-NC-Pad6)") (class "Default")
      (node (ref "4") (pin "6") (pinfunction "NC_6") (pintype "passive+no_connect"))
    )
    (net (code "85") (name "unconnected-(4-OUT4-Pad19)") (class "Default")
      (node (ref "4") (pin "19") (pinfunction "OUT4_19") (pintype "passive"))
    )
    (net (code "86") (name "unconnected-(CN1-Pad1)") (class "Default")
      (node (ref "CN1") (pin "1") (pinfunction "1_1") (pintype "passive+no_connect"))
    )
    (net (code "87") (name "unconnected-(CN1-Pad2)") (class "Default")
      (node (ref "CN1") (pin "2") (pinfunction "2_2") (pintype "passive+no_connect"))
    )
    (net (code "88") (name "unconnected-(J5-Pad1)") (class "Default")
      (node (ref "J5") (pin "1") (pinfunction "1_1") (pintype "passive"))
    )
    (net (code "89") (name "unconnected-(J5-Pad2)") (class "Default")
      (node (ref "J5") (pin "2") (pinfunction "2_2") (pintype "passive"))
    )
    (net (code "90") (name "unconnected-(J6-Pad5)") (class "Default")
      (node (ref "J6") (pin "5") (pinfunction "5_5") (pintype "passive"))
    )
    (net (code "91") (name "unconnected-(J6-Pad6)") (class "Default")
      (node (ref "J6") (pin "6") (pinfunction "6_6") (pintype "passive"))
    )
  )
)
